# USB.net
KiCad netlist of a schematic drawn in Altium Designer
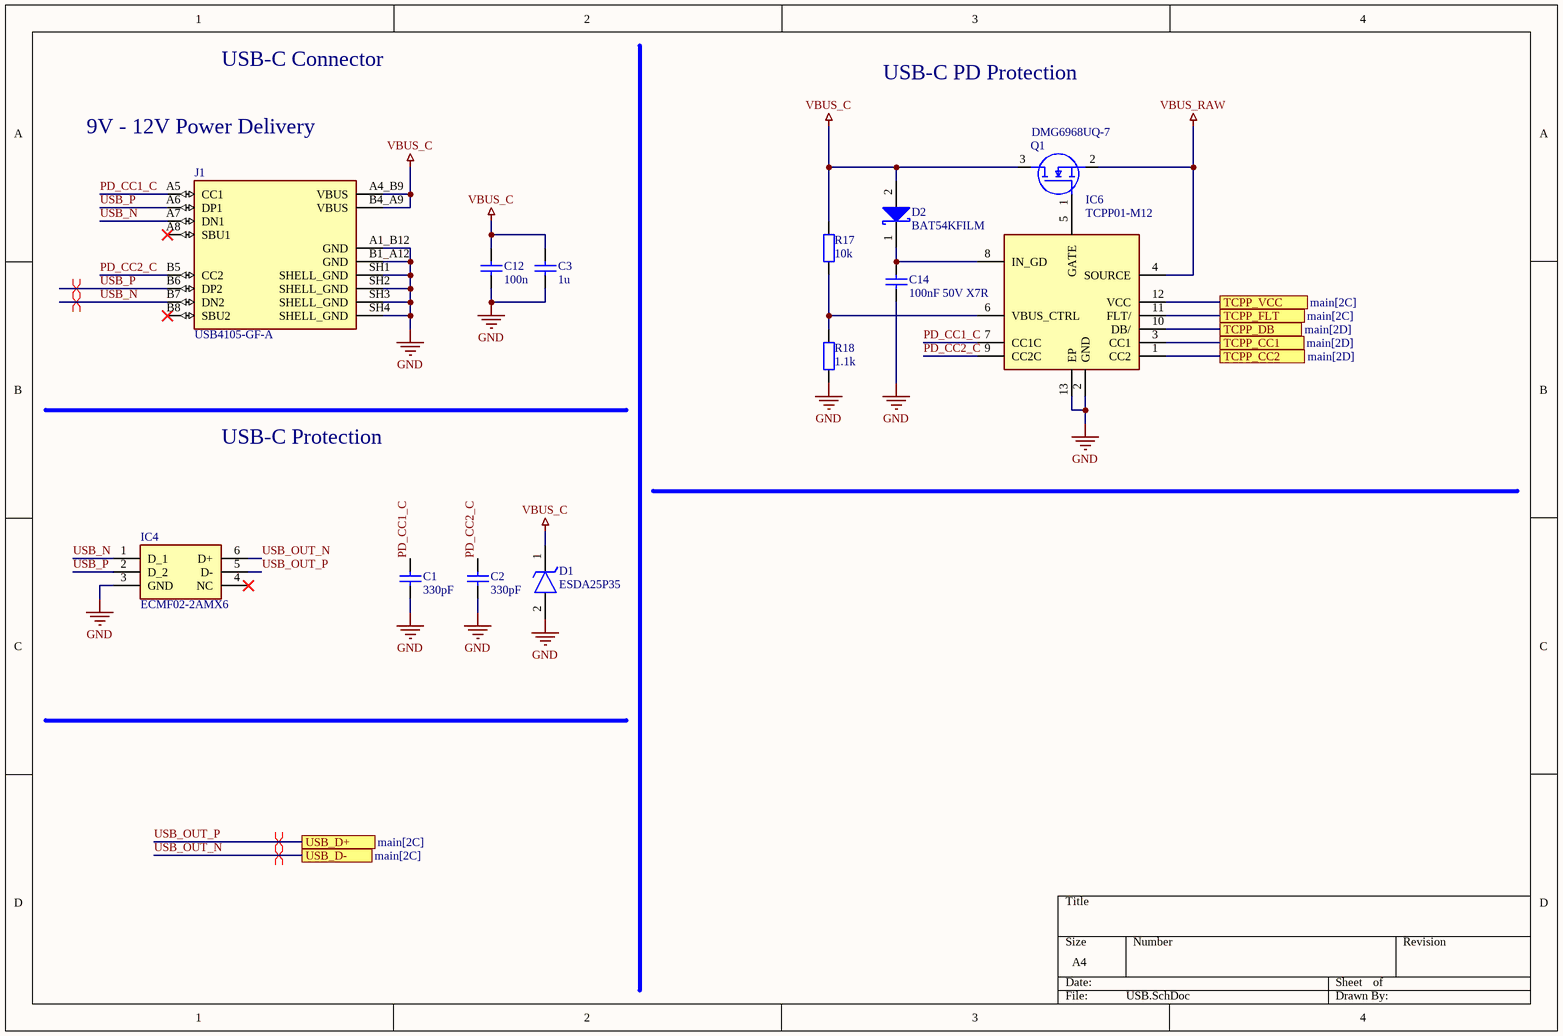
[diagram p0: USB.SchDoc]

(export (version "E")
  (design (tool "Eeschema 10.0.6"))
  (components
    (comp (ref "C1")
      (value "330pF")
      (footprint "Miscellaneous Devices:1608[0603]")
      (description "Capacitor")
      (fields (field (name "PUBLISHER") "Altium Limited"))
      (libsource (lib "Miscellaneous Devices") (part "Cap"))
    )
    (comp (ref "C2")
      (value "330pF")
      (footprint "Miscellaneous Devices:1608[0603]")
      (description "Capacitor")
      (fields (field (name "PUBLISHER") "Altium Limited"))
      (libsource (lib "Miscellaneous Devices") (part "Cap"))
    )
    (comp (ref "C3")
      (value "1u")
      (footprint "Miscellaneous Devices:1608[0603]")
      (description "Capacitor")
      (fields (field (name "PUBLISHER") "Altium Limited"))
      (libsource (lib "Miscellaneous Devices") (part "Cap"))
    )
    (comp (ref "C12")
      (value "100n")
      (footprint "Miscellaneous Devices:1608[0603]")
      (description "Capacitor")
      (fields (field (name "PUBLISHER") "Altium Limited"))
      (libsource (lib "Miscellaneous Devices") (part "Cap"))
    )
    (comp (ref "C14")
      (value "100nF 50V X7R")
      (footprint "Miscellaneous Devices:1608[0603]")
      (description "50 V X7R 100 nF capacitor")
      (fields (field (name "PUBLISHER") "Altium Limited"))
      (libsource (lib "Miscellaneous Devices") (part "Cap"))
    )
    (comp (ref "D1")
      (value "ESDA25P35")
      (footprint "Lib_VFD_Clock:ESDA25P351U1M")
      (description "TVS Diode (Uni-directional)")
      (fields
        (field (name "MANUFACTURER_PART_NUMBER") "ESDA25P35-1U1M")
        (field (name "MOUSER PART NUMBER") "511-ESDA25P35-1U1M")
      )
      (libsource (lib "Lib_VFD_Clock") (part "ESDA25P35-1U1M"))
    )
    (comp (ref "D2")
      (value "BAT54KFILM")
      (footprint "Lib_VFD_Clock:SODFL1608X70N")
      (description "Diode")
      (fields (field (name "MOUSER PART NUMBER") "511-BAT54KFILM"))
      (libsource (lib "Lib_VFD_Clock") (part "BAT54KFILM"))
    )
    (comp (ref "IC4")
      (value "ECMF02-2AMX6")
      (footprint "Lib_VFD_Clock:SON50P150X170X55-6N-D")
      (description "Integrated Circuit")
      (fields (field (name "MOUSER PART NUMBER") "511-ECMF02-2AMX6"))
      (libsource (lib "Lib_VFD_Clock") (part "ECMF02-2AMX6"))
    )
    (comp (ref "IC6")
      (value "TCPP01-M12")
      (footprint "Lib_VFD_Clock:QFN50P300X300X100-13N-D")
      (description "Integrated Circuit")
      (fields (field (name "MOUSER PART NUMBER") "511-TCPP01-M12"))
      (libsource (lib "Lib_VFD_Clock") (part "TCPP01-M12"))
    )
    (comp (ref "J1")
      (value "USB4105-GF-A")
      (footprint "GCT_USB4105-GF-A")
      (fields (field (name "MF") "{'manufacturer': u'GCT'}"))
      (libsource (lib "Lib_VFD_Clock") (part "USB4105-GF-A"))
    )
    (comp (ref "Q1")
      (value "DMG6968UQ-7")
      (footprint "Lib_VFD_Clock:SOT96P240X110-3N")
      (description "MOSFET (N-Channel)")
      (fields (field (name "MOUSER PART NUMBER") "621-DMG6968UQ-7"))
      (libsource (lib "Lib_VFD_Clock") (part "DMG6968UQ-7"))
    )
    (comp (ref "R17")
      (value "10k")
      (footprint "Miscellaneous Devices:J1-0603")
      (description "Resistor")
      (fields (field (name "PUBLISHER") "Altium Limited"))
      (libsource (lib "Miscellaneous Devices") (part "Res2"))
    )
    (comp (ref "R18")
      (value "1.1k")
      (footprint "Miscellaneous Devices:J1-0603")
      (description "Resistor")
      (fields (field (name "PUBLISHER") "Altium Limited"))
      (libsource (lib "Miscellaneous Devices") (part "Res2"))
    )
  )
  (nets
    (net (code "1") (name "/PD_CC1_C") (class "Default")
      (node (ref "C1") (pin "2") (pinfunction "2_2") (pintype "passive"))
      (node (ref "IC6") (pin "7") (pinfunction "CC1C_7") (pintype "passive"))
      (node (ref "J1") (pin "A5") (pinfunction "CC1_A5") (pintype "bidirectional"))
    )
    (net (code "2") (name "/PD_CC2_C") (class "Default")
      (node (ref "C2") (pin "2") (pinfunction "2_2") (pintype "passive"))
      (node (ref "IC6") (pin "9") (pinfunction "CC2C_9") (pintype "passive"))
      (node (ref "J1") (pin "B5") (pinfunction "CC2_B5") (pintype "bidirectional"))
    )
    (net (code "3") (name "/TCPP_CC1") (class "Default")
      (node (ref "IC6") (pin "3") (pinfunction "CC1_3") (pintype "passive"))
    )
    (net (code "4") (name "/TCPP_CC2") (class "Default")
      (node (ref "IC6") (pin "1") (pinfunction "CC2_1") (pintype "passive"))
    )
    (net (code "5") (name "/TCPP_DB") (class "Default")
      (node (ref "IC6") (pin "10") (pinfunction "DB/_10") (pintype "passive"))
    )
    (net (code "6") (name "/TCPP_FLT") (class "Default")
      (node (ref "IC6") (pin "11") (pinfunction "FLT/_11") (pintype "passive"))
    )
    (net (code "7") (name "/TCPP_VCC") (class "Default")
      (node (ref "IC6") (pin "12") (pinfunction "VCC_12") (pintype "passive"))
    )
    (net (code "8") (name "/USB_N") (class "Default")
      (node (ref "IC4") (pin "1") (pinfunction "D_1_1") (pintype "passive"))
      (node (ref "J1") (pin "A7") (pinfunction "DN1_A7") (pintype "bidirectional"))
      (node (ref "J1") (pin "B7") (pinfunction "DN2_B7") (pintype "bidirectional"))
    )
    (net (code "9") (name "/USB_OUT_N") (class "Default")
      (node (ref "IC4") (pin "6") (pinfunction "D+_6") (pintype "passive"))
    )
    (net (code "10") (name "/USB_OUT_P") (class "Default")
      (node (ref "IC4") (pin "5") (pinfunction "D-_5") (pintype "passive"))
    )
    (net (code "11") (name "/USB_P") (class "Default")
      (node (ref "IC4") (pin "2") (pinfunction "D_2_2") (pintype "passive"))
      (node (ref "J1") (pin "A6") (pinfunction "DP1_A6") (pintype "bidirectional"))
      (node (ref "J1") (pin "B6") (pinfunction "DP2_B6") (pintype "bidirectional"))
    )
    (net (code "12") (name "GND") (class "Default")
      (node (ref "C1") (pin "1") (pinfunction "1_1") (pintype "passive"))
      (node (ref "C12") (pin "1") (pinfunction "1_1") (pintype "passive"))
      (node (ref "C14") (pin "1") (pinfunction "1_1") (pintype "passive"))
      (node (ref "C2") (pin "1") (pinfunction "1_1") (pintype "passive"))
      (node (ref "C3") (pin "1") (pinfunction "1_1") (pintype "passive"))
      (node (ref "D1") (pin "2") (pinfunction "A_2") (pintype "passive"))
      (node (ref "IC4") (pin "3") (pinfunction "GND_3") (pintype "passive"))
      (node (ref "IC6") (pin "13") (pinfunction "EP_13") (pintype "passive"))
      (node (ref "IC6") (pin "2") (pinfunction "GND_2") (pintype "passive"))
      (node (ref "J1") (pin "A1_B12") (pinfunction "GND_A1_B12") (pintype "power_in"))
      (node (ref "J1") (pin "B1_A12") (pinfunction "GND_B1_A12") (pintype "power_in"))
      (node (ref "J1") (pin "SH1") (pinfunction "SHELL_GND_SH1") (pintype "power_in"))
      (node (ref "J1") (pin "SH2") (pinfunction "SHELL_GND_SH2") (pintype "power_in"))
      (node (ref "J1") (pin "SH3") (pinfunction "SHELL_GND_SH3") (pintype "power_in"))
      (node (ref "J1") (pin "SH4") (pinfunction "SHELL_GND_SH4") (pintype "power_in"))
      (node (ref "R18") (pin "1") (pinfunction "1_1") (pintype "passive"))
    )
    (net (code "13") (name "Net-(D2-K)") (class "Default")
      (node (ref "C14") (pin "2") (pinfunction "2_2") (pintype "passive"))
      (node (ref "D2") (pin "1") (pinfunction "K_1") (pintype "passive"))
      (node (ref "IC6") (pin "8") (pinfunction "IN_GD_8") (pintype "passive"))
    )
    (net (code "14") (name "Net-(IC6-GATE)") (class "Default")
      (node (ref "IC6") (pin "5") (pinfunction "GATE_5") (pintype "passive"))
      (node (ref "Q1") (pin "1") (pinfunction "G_1") (pintype "passive"))
    )
    (net (code "15") (name "Net-(IC6-VBUS_CTRL)") (class "Default")
      (node (ref "IC6") (pin "6") (pinfunction "VBUS_CTRL_6") (pintype "passive"))
      (node (ref "R17") (pin "1") (pinfunction "1_1") (pintype "passive"))
      (node (ref "R18") (pin "2") (pinfunction "2_2") (pintype "passive"))
    )
    (net (code "16") (name "VBUS_C") (class "Default")
      (node (ref "C12") (pin "2") (pinfunction "2_2") (pintype "passive"))
      (node (ref "C3") (pin "2") (pinfunction "2_2") (pintype "passive"))
      (node (ref "D1") (pin "1") (pinfunction "K_1") (pintype "passive"))
      (node (ref "D2") (pin "2") (pinfunction "A_2") (pintype "passive"))
      (node (ref "J1") (pin "A4_B9") (pinfunction "VBUS_A4_B9") (pintype "power_in"))
      (node (ref "J1") (pin "B4_A9") (pinfunction "VBUS_B4_A9") (pintype "power_in"))
      (node (ref "Q1") (pin "3") (pinfunction "D_3") (pintype "passive"))
      (node (ref "R17") (pin "2") (pinfunction "2_2") (pintype "passive"))
    )
    (net (code "17") (name "VBUS_RAW") (class "Default")
      (node (ref "IC6") (pin "4") (pinfunction "SOURCE_4") (pintype "passive"))
      (node (ref "Q1") (pin "2") (pinfunction "S_2") (pintype "passive"))
    )
    (net (code "18") (name "unconnected-(IC4-NC-Pad4)") (class "Default")
      (node (ref "IC4") (pin "4") (pinfunction "NC_4") (pintype "passive+no_connect"))
    )
    (net (code "19") (name "unconnected-(J1-SBU1-PadA8)") (class "Default")
      (node (ref "J1") (pin "A8") (pinfunction "SBU1_A8") (pintype "bidirectional+no_connect"))
    )
    (net (code "20") (name "unconnected-(J1-SBU2-PadB8)") (class "Default")
      (node (ref "J1") (pin "B8") (pinfunction "SBU2_B8") (pintype "bidirectional+no_connect"))
    )
  )
)
